# F200s.net
KiCad netlist of a schematic drawn in Altium Designer
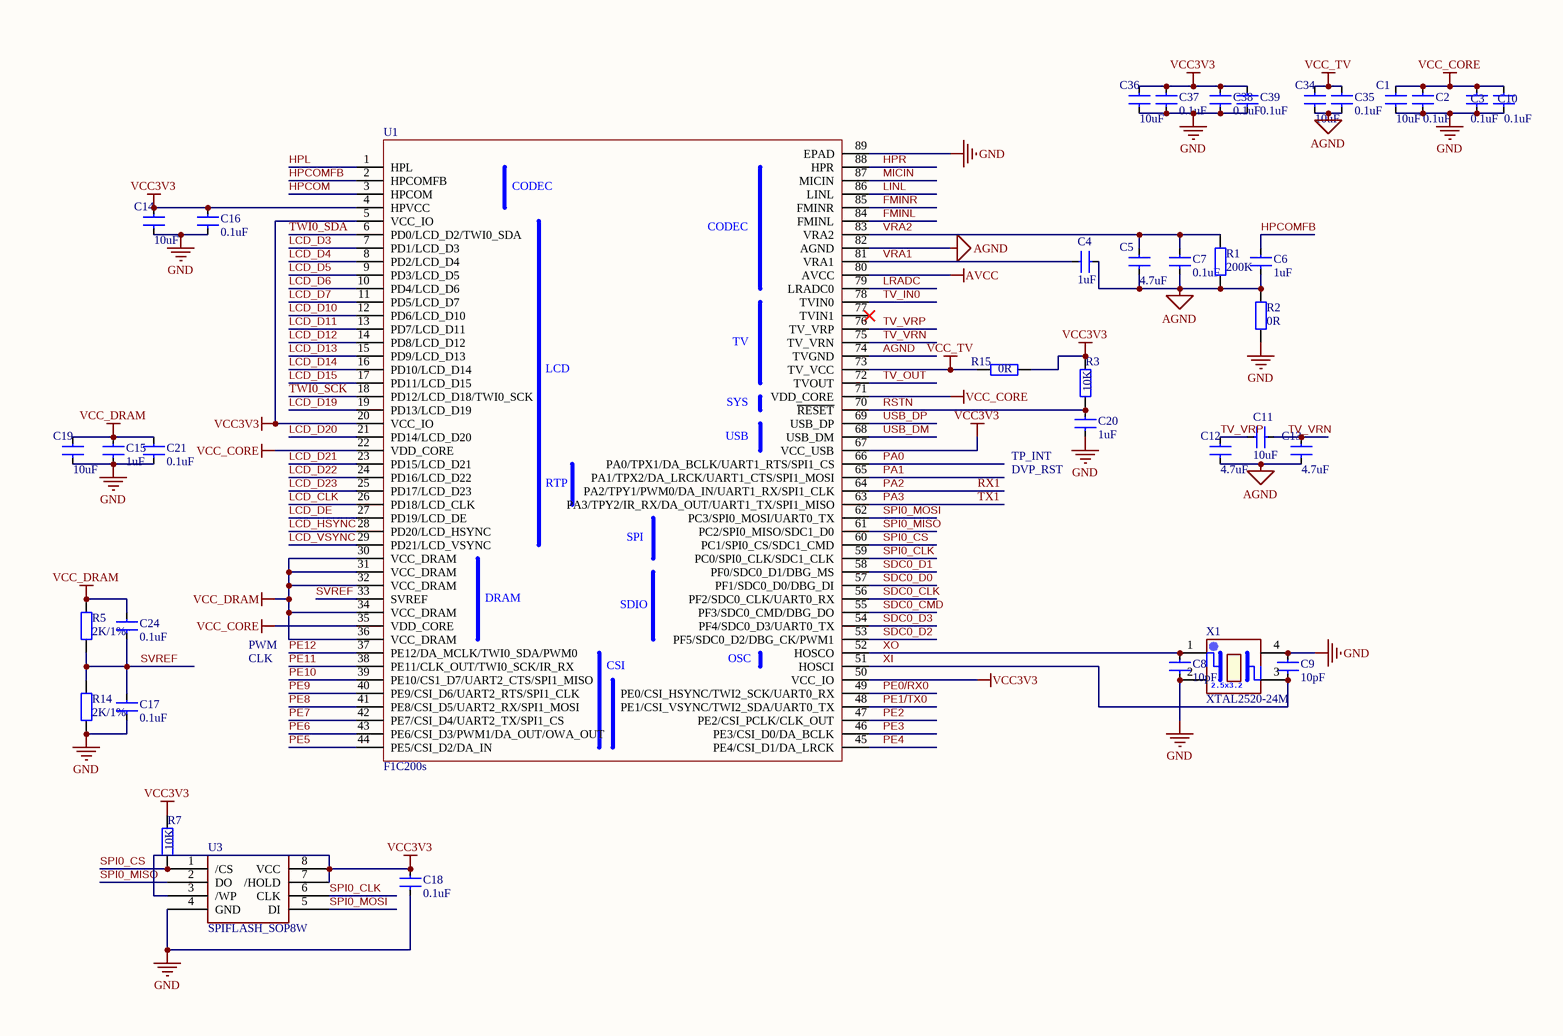
[diagram p0: F200s.SchDoc]

(export (version "E")
  (design (tool "Eeschema 10.0.6"))
  (components
    (comp (ref "C1")
      (value "10uF")
      (footprint "C0402")
      (description "普通小电容")
      (libsource (lib "LIB_MANGO") (part "CAP"))
    )
    (comp (ref "C2")
      (value "0.1uF")
      (footprint "C0402")
      (description "普通小电容")
      (libsource (lib "LIB_MANGO") (part "CAP"))
    )
    (comp (ref "C3")
      (value "0.1uF")
      (footprint "C0402")
      (description "普通小电容")
      (libsource (lib "LIB_MANGO") (part "CAP"))
    )
    (comp (ref "C4")
      (value "1uF")
      (footprint "C0402")
      (description "普通小电容")
      (libsource (lib "LIB_MANGO") (part "CAP"))
    )
    (comp (ref "C5")
      (value "4.7uF")
      (footprint "C0402")
      (description "普通小电容")
      (libsource (lib "LIB_MANGO") (part "CAP"))
    )
    (comp (ref "C6")
      (value "1uF")
      (footprint "C0402")
      (description "普通小电容")
      (libsource (lib "LIB_MANGO") (part "CAP"))
    )
    (comp (ref "C7")
      (value "0.1uF")
      (footprint "C0402")
      (description "普通小电容")
      (libsource (lib "LIB_MANGO") (part "CAP"))
    )
    (comp (ref "C8")
      (value "10pF")
      (footprint "C0402")
      (description "普通小电容")
      (libsource (lib "LIB_MANGO") (part "CAP"))
    )
    (comp (ref "C9")
      (value "10pF")
      (footprint "C0402")
      (description "普通小电容")
      (libsource (lib "LIB_MANGO") (part "CAP"))
    )
    (comp (ref "C10")
      (value "0.1uF")
      (footprint "C0402")
      (description "普通小电容")
      (libsource (lib "LIB_MANGO") (part "CAP"))
    )
    (comp (ref "C11")
      (value "10uF")
      (footprint "C0402")
      (description "普通小电容")
      (libsource (lib "LIB_MANGO") (part "CAP"))
    )
    (comp (ref "C12")
      (value "4.7uF")
      (footprint "C0402")
      (description "普通小电容")
      (libsource (lib "LIB_MANGO") (part "CAP"))
    )
    (comp (ref "C13")
      (value "4.7uF")
      (footprint "C0402")
      (description "普通小电容")
      (libsource (lib "LIB_MANGO") (part "CAP"))
    )
    (comp (ref "C14")
      (value "10uF")
      (footprint "C0402")
      (description "普通小电容")
      (libsource (lib "LIB_MANGO") (part "CAP"))
    )
    (comp (ref "C15")
      (value "1uF")
      (footprint "C0402")
      (description "普通小电容")
      (libsource (lib "LIB_MANGO") (part "CAP"))
    )
    (comp (ref "C16")
      (value "0.1uF")
      (footprint "C0402")
      (description "普通小电容")
      (libsource (lib "LIB_MANGO") (part "CAP"))
    )
    (comp (ref "C17")
      (value "0.1uF")
      (footprint "C0402")
      (description "普通小电容")
      (libsource (lib "LIB_MANGO") (part "CAP"))
    )
    (comp (ref "C18")
      (value "0.1uF")
      (footprint "C0402")
      (description "普通小电容")
      (libsource (lib "LIB_MANGO") (part "CAP"))
    )
    (comp (ref "C19")
      (value "10uF")
      (footprint "C0402")
      (description "普通小电容")
      (libsource (lib "LIB_MANGO") (part "CAP"))
    )
    (comp (ref "C20")
      (value "1uF")
      (footprint "C0402")
      (description "普通小电容")
      (libsource (lib "LIB_MANGO") (part "CAP"))
    )
    (comp (ref "C21")
      (value "0.1uF")
      (footprint "C0402")
      (description "普通小电容")
      (libsource (lib "LIB_MANGO") (part "CAP"))
    )
    (comp (ref "C24")
      (value "0.1uF")
      (footprint "C0402")
      (description "普通小电容")
      (libsource (lib "LIB_MANGO") (part "CAP"))
    )
    (comp (ref "C34")
      (value "10uF")
      (footprint "C0402")
      (description "普通小电容")
      (libsource (lib "LIB_MANGO") (part "CAP"))
    )
    (comp (ref "C35")
      (value "0.1uF")
      (footprint "C0402")
      (description "普通小电容")
      (libsource (lib "LIB_MANGO") (part "CAP"))
    )
    (comp (ref "C36")
      (value "10uF")
      (footprint "C0402")
      (description "普通小电容")
      (libsource (lib "LIB_MANGO") (part "CAP"))
    )
    (comp (ref "C37")
      (value "0.1uF")
      (footprint "C0402")
      (description "普通小电容")
      (libsource (lib "LIB_MANGO") (part "CAP"))
    )
    (comp (ref "C38")
      (value "0.1uF")
      (footprint "C0402")
      (description "普通小电容")
      (libsource (lib "LIB_MANGO") (part "CAP"))
    )
    (comp (ref "C39")
      (value "0.1uF")
      (footprint "C0402")
      (description "普通小电容")
      (libsource (lib "LIB_MANGO") (part "CAP"))
    )
    (comp (ref "R1")
      (value "200K")
      (footprint "R0402")
      (description "普通电阻")
      (libsource (lib "LIB_MANGO") (part "RES"))
    )
    (comp (ref "R2")
      (value "0R")
      (footprint "R0402")
      (description "普通电阻")
      (libsource (lib "LIB_MANGO") (part "RES"))
    )
    (comp (ref "R3")
      (value "10K")
      (footprint "R0402")
      (description "普通电阻")
      (libsource (lib "LIB_MANGO") (part "RES"))
    )
    (comp (ref "R5")
      (value "2K/1%")
      (footprint "R0402")
      (description "普通电阻")
      (libsource (lib "LIB_MANGO") (part "RES"))
    )
    (comp (ref "R7")
      (value "10K")
      (footprint "R0402")
      (description "普通电阻")
      (libsource (lib "LIB_MANGO") (part "RES"))
    )
    (comp (ref "R14")
      (value "2K/1%")
      (footprint "R0402")
      (description "普通电阻")
      (libsource (lib "LIB_MANGO") (part "RES"))
    )
    (comp (ref "R15")
      (value "0R")
      (footprint "R0402")
      (description "普通电阻")
      (libsource (lib "") (part "RES_1"))
    )
    (comp (ref "U1")
      (value "F1C200s")
      (footprint "QFN40P1000X1000X85_HS-89N")
      (libsource (lib "A") (part "F1C200s"))
    )
    (comp (ref "U3")
      (value "SPIFLASH_SOP8W")
      (footprint "WSON-SPIFLASH")
      (libsource (lib "LIB_MANGO") (part "SPIFLASH_SOP8W"))
    )
    (comp (ref "X1")
      (value "XTAL2520-24M")
      (footprint "XTAL2520")
      (libsource (lib "LIB_MANGO") (part "XTAL3225"))
    )
  )
  (nets
    (net (code "1") (name "/FMINL") (class "Default")
      (node (ref "U1") (pin "84") (pinfunction "FMINL_84") (pintype "passive"))
    )
    (net (code "2") (name "/FMINR") (class "Default")
      (node (ref "U1") (pin "85") (pinfunction "FMINR_85") (pintype "passive"))
    )
    (net (code "3") (name "/HPCOM") (class "Default")
      (node (ref "U1") (pin "3") (pinfunction "HPCOM_3") (pintype "passive"))
    )
    (net (code "4") (name "/HPCOMFB") (class "Default")
      (node (ref "C6") (pin "1") (pinfunction "1_1") (pintype "passive"))
      (node (ref "U1") (pin "2") (pinfunction "HPCOMFB_2") (pintype "passive"))
    )
    (net (code "5") (name "/HPL") (class "Default")
      (node (ref "U1") (pin "1") (pinfunction "HPL_1") (pintype "passive"))
    )
    (net (code "6") (name "/HPR") (class "Default")
      (node (ref "U1") (pin "88") (pinfunction "HPR_88") (pintype "passive"))
    )
    (net (code "7") (name "/LCD_CLK") (class "Default")
      (node (ref "U1") (pin "26") (pinfunction "PD18/LCD_CLK_26") (pintype "passive"))
    )
    (net (code "8") (name "/LCD_D3") (class "Default")
      (node (ref "U1") (pin "7") (pinfunction "PD1/LCD_D3_7") (pintype "passive"))
    )
    (net (code "9") (name "/LCD_D4") (class "Default")
      (node (ref "U1") (pin "8") (pinfunction "PD2/LCD_D4_8") (pintype "passive"))
    )
    (net (code "10") (name "/LCD_D5") (class "Default")
      (node (ref "U1") (pin "9") (pinfunction "PD3/LCD_D5_9") (pintype "passive"))
    )
    (net (code "11") (name "/LCD_D6") (class "Default")
      (node (ref "U1") (pin "10") (pinfunction "PD4/LCD_D6_10") (pintype "passive"))
    )
    (net (code "12") (name "/LCD_D7") (class "Default")
      (node (ref "U1") (pin "11") (pinfunction "PD5/LCD_D7_11") (pintype "passive"))
    )
    (net (code "13") (name "/LCD_D10") (class "Default")
      (node (ref "U1") (pin "12") (pinfunction "PD6/LCD_D10_12") (pintype "passive"))
    )
    (net (code "14") (name "/LCD_D11") (class "Default")
      (node (ref "U1") (pin "13") (pinfunction "PD7/LCD_D11_13") (pintype "passive"))
    )
    (net (code "15") (name "/LCD_D12") (class "Default")
      (node (ref "U1") (pin "14") (pinfunction "PD8/LCD_D12_14") (pintype "passive"))
    )
    (net (code "16") (name "/LCD_D13") (class "Default")
      (node (ref "U1") (pin "15") (pinfunction "PD9/LCD_D13_15") (pintype "passive"))
    )
    (net (code "17") (name "/LCD_D14") (class "Default")
      (node (ref "U1") (pin "16") (pinfunction "PD10/LCD_D14_16") (pintype "passive"))
    )
    (net (code "18") (name "/LCD_D15") (class "Default")
      (node (ref "U1") (pin "17") (pinfunction "PD11/LCD_D15_17") (pintype "passive"))
    )
    (net (code "19") (name "/LCD_D19") (class "Default")
      (node (ref "U1") (pin "19") (pinfunction "PD13/LCD_D19_19") (pintype "passive"))
    )
    (net (code "20") (name "/LCD_D20") (class "Default")
      (node (ref "U1") (pin "21") (pinfunction "PD14/LCD_D20_21") (pintype "passive"))
    )
    (net (code "21") (name "/LCD_D21") (class "Default")
      (node (ref "U1") (pin "23") (pinfunction "PD15/LCD_D21_23") (pintype "passive"))
    )
    (net (code "22") (name "/LCD_D22") (class "Default")
      (node (ref "U1") (pin "24") (pinfunction "PD16/LCD_D22_24") (pintype "passive"))
    )
    (net (code "23") (name "/LCD_D23") (class "Default")
      (node (ref "U1") (pin "25") (pinfunction "PD17/LCD_D23_25") (pintype "passive"))
    )
    (net (code "24") (name "/LCD_DE") (class "Default")
      (node (ref "U1") (pin "27") (pinfunction "PD19/LCD_DE_27") (pintype "passive"))
    )
    (net (code "25") (name "/LCD_HSYNC") (class "Default")
      (node (ref "U1") (pin "28") (pinfunction "PD20/LCD_HSYNC_28") (pintype "passive"))
    )
    (net (code "26") (name "/LCD_VSYNC") (class "Default")
      (node (ref "U1") (pin "29") (pinfunction "PD21/LCD_VSYNC_29") (pintype "passive"))
    )
    (net (code "27") (name "/LINL") (class "Default")
      (node (ref "U1") (pin "86") (pinfunction "LINL_86") (pintype "passive"))
    )
    (net (code "28") (name "/LRADC") (class "Default")
      (node (ref "U1") (pin "79") (pinfunction "LRADC0_79") (pintype "passive"))
    )
    (net (code "29") (name "/MICIN") (class "Default")
      (node (ref "U1") (pin "87") (pinfunction "MICIN_87") (pintype "passive"))
    )
    (net (code "30") (name "/PA0") (class "Default")
      (node (ref "U1") (pin "66") (pinfunction "PA0/TPX1/DA_BCLK/UART1_RTS/SPI1_CS_66") (pintype "passive"))
    )
    (net (code "31") (name "/PA1") (class "Default")
      (node (ref "U1") (pin "65") (pinfunction "PA1/TPX2/DA_LRCK/UART1_CTS/SPI1_MOSI_65") (pintype "passive"))
    )
    (net (code "32") (name "/PA2") (class "Default")
      (node (ref "U1") (pin "64") (pinfunction "PA2/TPY1/PWM0/DA_IN/UART1_RX/SPI1_CLK_64") (pintype "passive"))
    )
    (net (code "33") (name "/PA3") (class "Default")
      (node (ref "U1") (pin "63") (pinfunction "PA3/TPY2/IR_RX/DA_OUT/UART1_TX/SPI1_MISO_63") (pintype "passive"))
    )
    (net (code "34") (name "/PE0{slash}RX0") (class "Default")
      (node (ref "U1") (pin "49") (pinfunction "PE0/CSI_HSYNC/TWI2_SCK/UART0_RX_49") (pintype "passive"))
    )
    (net (code "35") (name "/PE1{slash}TX0") (class "Default")
      (node (ref "U1") (pin "48") (pinfunction "PE1/CSI_VSYNC/TWI2_SDA/UART0_TX_48") (pintype "passive"))
    )
    (net (code "36") (name "/PE2") (class "Default")
      (node (ref "U1") (pin "47") (pinfunction "PE2/CSI_PCLK/CLK_OUT_47") (pintype "passive"))
    )
    (net (code "37") (name "/PE3") (class "Default")
      (node (ref "U1") (pin "46") (pinfunction "PE3/CSI_D0/DA_BCLK_46") (pintype "passive"))
    )
    (net (code "38") (name "/PE4") (class "Default")
      (node (ref "U1") (pin "45") (pinfunction "PE4/CSI_D1/DA_LRCK_45") (pintype "passive"))
    )
    (net (code "39") (name "/PE5") (class "Default")
      (node (ref "U1") (pin "44") (pinfunction "PE5/CSI_D2/DA_IN_44") (pintype "passive"))
    )
    (net (code "40") (name "/PE6") (class "Default")
      (node (ref "U1") (pin "43") (pinfunction "PE6/CSI_D3/PWM1/DA_OUT/OWA_OUT_43") (pintype "passive"))
    )
    (net (code "41") (name "/PE7") (class "Default")
      (node (ref "U1") (pin "42") (pinfunction "PE7/CSI_D4/UART2_TX/SPI1_CS_42") (pintype "passive"))
    )
    (net (code "42") (name "/PE8") (class "Default")
      (node (ref "U1") (pin "41") (pinfunction "PE8/CSI_D5/UART2_RX/SPI1_MOSI_41") (pintype "passive"))
    )
    (net (code "43") (name "/PE9") (class "Default")
      (node (ref "U1") (pin "40") (pinfunction "PE9/CSI_D6/UART2_RTS/SPI1_CLK_40") (pintype "passive"))
    )
    (net (code "44") (name "/PE10") (class "Default")
      (node (ref "U1") (pin "39") (pinfunction "PE10/CS1_D7/UART2_CTS/SPI1_MISO_39") (pintype "passive"))
    )
    (net (code "45") (name "/PE11") (class "Default")
      (node (ref "U1") (pin "38") (pinfunction "PE11/CLK_OUT/TWI0_SCK/IR_RX_38") (pintype "passive"))
    )
    (net (code "46") (name "/PE12") (class "Default")
      (node (ref "U1") (pin "37") (pinfunction "PE12/DA_MCLK/TWI0_SDA/PWM0_37") (pintype "passive"))
    )
    (net (code "47") (name "/RSTN") (class "Default")
      (node (ref "C20") (pin "1") (pinfunction "1_1") (pintype "passive"))
      (node (ref "R3") (pin "1") (pinfunction "1_1") (pintype "passive"))
      (node (ref "U1") (pin "70") (pinfunction "~{RESET}_70") (pintype "passive"))
    )
    (net (code "48") (name "/SDC0_CLK") (class "Default")
      (node (ref "U1") (pin "56") (pinfunction "PF2/SDC0_CLK/UART0_RX_56") (pintype "passive"))
    )
    (net (code "49") (name "/SDC0_CMD") (class "Default")
      (node (ref "U1") (pin "55") (pinfunction "PF3/SDC0_CMD/DBG_DO_55") (pintype "passive"))
    )
    (net (code "50") (name "/SDC0_D0") (class "Default")
      (node (ref "U1") (pin "57") (pinfunction "PF1/SDC0_D0/DBG_DI_57") (pintype "passive"))
    )
    (net (code "51") (name "/SDC0_D1") (class "Default")
      (node (ref "U1") (pin "58") (pinfunction "PF0/SDC0_D1/DBG_MS_58") (pintype "passive"))
    )
    (net (code "52") (name "/SDC0_D2") (class "Default")
      (node (ref "U1") (pin "53") (pinfunction "PF5/SDC0_D2/DBG_CK/PWM1_53") (pintype "passive"))
    )
    (net (code "53") (name "/SDC0_D3") (class "Default")
      (node (ref "U1") (pin "54") (pinfunction "PF4/SDC0_D3/UART0_TX_54") (pintype "passive"))
    )
    (net (code "54") (name "/SPI0_CLK") (class "Default")
      (node (ref "U1") (pin "59") (pinfunction "PC0/SPI0_CLK/SDC1_CLK_59") (pintype "passive"))
      (node (ref "U3") (pin "6") (pinfunction "CLK_6") (pintype "passive"))
    )
    (net (code "55") (name "/SPI0_CS") (class "Default")
      (node (ref "R7") (pin "1") (pinfunction "1_1") (pintype "passive"))
      (node (ref "U1") (pin "60") (pinfunction "PC1/SPI0_CS/SDC1_CMD_60") (pintype "passive"))
      (node (ref "U3") (pin "1") (pinfunction "/CS_1") (pintype "passive"))
    )
    (net (code "56") (name "/SPI0_MISO") (class "Default")
      (node (ref "U1") (pin "61") (pinfunction "PC2/SPI0_MISO/SDC1_D0_61") (pintype "passive"))
      (node (ref "U3") (pin "2") (pinfunction "DO_2") (pintype "passive"))
    )
    (net (code "57") (name "/SPI0_MOSI") (class "Default")
      (node (ref "U1") (pin "62") (pinfunction "PC3/SPI0_MOSI/UART0_TX_62") (pintype "passive"))
      (node (ref "U3") (pin "5") (pinfunction "DI_5") (pintype "passive"))
    )
    (net (code "58") (name "/SVREF") (class "Default")
      (node (ref "C17") (pin "2") (pinfunction "2_2") (pintype "passive"))
      (node (ref "C24") (pin "1") (pinfunction "1_1") (pintype "passive"))
      (node (ref "R14") (pin "2") (pinfunction "2_2") (pintype "passive"))
      (node (ref "R5") (pin "1") (pinfunction "1_1") (pintype "passive"))
      (node (ref "U1") (pin "33") (pinfunction "SVREF_33") (pintype "passive"))
    )
    (net (code "59") (name "/TV_IN0") (class "Default")
      (node (ref "U1") (pin "78") (pinfunction "TVIN0_78") (pintype "passive"))
    )
    (net (code "60") (name "/TV_OUT") (class "Default")
      (node (ref "U1") (pin "72") (pinfunction "TVOUT_72") (pintype "passive"))
    )
    (net (code "61") (name "/TV_VRN") (class "Default")
      (node (ref "C11") (pin "1") (pinfunction "1_1") (pintype "passive"))
      (node (ref "C13") (pin "2") (pinfunction "2_2") (pintype "passive"))
      (node (ref "U1") (pin "75") (pinfunction "TV_VRN_75") (pintype "passive"))
    )
    (net (code "62") (name "/TV_VRP") (class "Default")
      (node (ref "C11") (pin "2") (pinfunction "2_2") (pintype "passive"))
      (node (ref "C12") (pin "2") (pinfunction "2_2") (pintype "passive"))
      (node (ref "U1") (pin "76") (pinfunction "TV_VRP_76") (pintype "passive"))
    )
    (net (code "63") (name "/TWI0_SCK") (class "Default")
      (node (ref "U1") (pin "18") (pinfunction "PD12/LCD_D18/TWI0_SCK_18") (pintype "passive"))
    )
    (net (code "64") (name "/TWI0_SDA") (class "Default")
      (node (ref "U1") (pin "6") (pinfunction "PD0/LCD_D2/TWI0_SDA_6") (pintype "passive"))
    )
    (net (code "65") (name "/USB_DM") (class "Default")
      (node (ref "U1") (pin "68") (pinfunction "USB_DM_68") (pintype "passive"))
    )
    (net (code "66") (name "/USB_DP") (class "Default")
      (node (ref "U1") (pin "69") (pinfunction "USB_DP_69") (pintype "passive"))
    )
    (net (code "67") (name "/VRA1") (class "Default")
      (node (ref "C4") (pin "1") (pinfunction "1_1") (pintype "passive"))
      (node (ref "U1") (pin "81") (pinfunction "VRA1_81") (pintype "passive"))
    )
    (net (code "68") (name "/VRA2") (class "Default")
      (node (ref "C5") (pin "2") (pinfunction "2_2") (pintype "passive"))
      (node (ref "C7") (pin "2") (pinfunction "2_2") (pintype "passive"))
      (node (ref "R1") (pin "2") (pinfunction "2_2") (pintype "passive"))
      (node (ref "U1") (pin "83") (pinfunction "VRA2_83") (pintype "passive"))
    )
    (net (code "69") (name "/XI") (class "Default")
      (node (ref "C9") (pin "1") (pinfunction "1_1") (pintype "passive"))
      (node (ref "U1") (pin "51") (pinfunction "HOSCI_51") (pintype "passive"))
      (node (ref "X1") (pin "3") (pinfunction "X2_3") (pintype "passive"))
    )
    (net (code "70") (name "/XO") (class "Default")
      (node (ref "C8") (pin "2") (pinfunction "2_2") (pintype "passive"))
      (node (ref "U1") (pin "52") (pinfunction "HOSCO_52") (pintype "passive"))
      (node (ref "X1") (pin "1") (pinfunction "X1_1") (pintype "passive"))
    )
    (net (code "71") (name "AGND") (class "Default")
      (node (ref "C12") (pin "1") (pinfunction "1_1") (pintype "passive"))
      (node (ref "C13") (pin "1") (pinfunction "1_1") (pintype "passive"))
      (node (ref "C34") (pin "1") (pinfunction "1_1") (pintype "passive"))
      (node (ref "C35") (pin "1") (pinfunction "1_1") (pintype "passive"))
      (node (ref "C4") (pin "2") (pinfunction "2_2") (pintype "passive"))
      (node (ref "C5") (pin "1") (pinfunction "1_1") (pintype "passive"))
      (node (ref "C6") (pin "2") (pinfunction "2_2") (pintype "passive"))
      (node (ref "C7") (pin "1") (pinfunction "1_1") (pintype "passive"))
      (node (ref "R1") (pin "1") (pinfunction "1_1") (pintype "passive"))
      (node (ref "R2") (pin "2") (pinfunction "2_2") (pintype "passive"))
      (node (ref "U1") (pin "74") (pinfunction "TVGND_74") (pintype "passive"))
      (node (ref "U1") (pin "82") (pinfunction "AGND_82") (pintype "passive"))
    )
    (net (code "72") (name "AVCC") (class "Default")
      (node (ref "U1") (pin "80") (pinfunction "AVCC_80") (pintype "passive"))
    )
    (net (code "73") (name "GND") (class "Default")
      (node (ref "C1") (pin "1") (pinfunction "1_1") (pintype "passive"))
      (node (ref "C10") (pin "1") (pinfunction "1_1") (pintype "passive"))
      (node (ref "C14") (pin "1") (pinfunction "1_1") (pintype "passive"))
      (node (ref "C15") (pin "1") (pinfunction "1_1") (pintype "passive"))
      (node (ref "C16") (pin "1") (pinfunction "1_1") (pintype "passive"))
      (node (ref "C17") (pin "1") (pinfunction "1_1") (pintype "passive"))
      (node (ref "C18") (pin "1") (pinfunction "1_1") (pintype "passive"))
      (node (ref "C19") (pin "1") (pinfunction "1_1") (pintype "passive"))
      (node (ref "C2") (pin "1") (pinfunction "1_1") (pintype "passive"))
      (node (ref "C20") (pin "2") (pinfunction "2_2") (pintype "passive"))
      (node (ref "C21") (pin "1") (pinfunction "1_1") (pintype "passive"))
      (node (ref "C3") (pin "1") (pinfunction "1_1") (pintype "passive"))
      (node (ref "C36") (pin "1") (pinfunction "1_1") (pintype "passive"))
      (node (ref "C37") (pin "1") (pinfunction "1_1") (pintype "passive"))
      (node (ref "C38") (pin "1") (pinfunction "1_1") (pintype "passive"))
      (node (ref "C39") (pin "1") (pinfunction "1_1") (pintype "passive"))
      (node (ref "C8") (pin "1") (pinfunction "1_1") (pintype "passive"))
      (node (ref "C9") (pin "2") (pinfunction "2_2") (pintype "passive"))
      (node (ref "R14") (pin "1") (pinfunction "1_1") (pintype "passive"))
      (node (ref "R2") (pin "1") (pinfunction "1_1") (pintype "passive"))
      (node (ref "U1") (pin "89") (pinfunction "EPAD_89") (pintype "passive"))
      (node (ref "U3") (pin "4") (pinfunction "GND_4") (pintype "passive"))
      (node (ref "X1") (pin "2") (pinfunction "NC1_2") (pintype "passive"))
      (node (ref "X1") (pin "4") (pinfunction "NC2_4") (pintype "passive"))
    )
    (net (code "74") (name "VCC3V3") (class "Default")
      (node (ref "C14") (pin "2") (pinfunction "2_2") (pintype "passive"))
      (node (ref "C16") (pin "2") (pinfunction "2_2") (pintype "passive"))
      (node (ref "C18") (pin "2") (pinfunction "2_2") (pintype "passive"))
      (node (ref "C36") (pin "2") (pinfunction "2_2") (pintype "passive"))
      (node (ref "C37") (pin "2") (pinfunction "2_2") (pintype "passive"))
      (node (ref "C38") (pin "2") (pinfunction "2_2") (pintype "passive"))
      (node (ref "C39") (pin "2") (pinfunction "2_2") (pintype "passive"))
      (node (ref "R15") (pin "1") (pinfunction "1_1") (pintype "passive"))
      (node (ref "R3") (pin "2") (pinfunction "2_2") (pintype "passive"))
      (node (ref "R7") (pin "2") (pinfunction "2_2") (pintype "passive"))
      (node (ref "U1") (pin "20") (pinfunction "VCC_IO_20") (pintype "passive"))
      (node (ref "U1") (pin "4") (pinfunction "HPVCC_4") (pintype "passive"))
      (node (ref "U1") (pin "5") (pinfunction "VCC_IO_5") (pintype "passive"))
      (node (ref "U1") (pin "50") (pinfunction "VCC_IO_50") (pintype "passive"))
      (node (ref "U1") (pin "67") (pinfunction "VCC_USB_67") (pintype "passive"))
      (node (ref "U3") (pin "3") (pinfunction "/WP_3") (pintype "passive"))
      (node (ref "U3") (pin "7") (pinfunction "/HOLD_7") (pintype "passive"))
      (node (ref "U3") (pin "8") (pinfunction "VCC_8") (pintype "passive"))
    )
    (net (code "75") (name "VCC_CORE") (class "Default")
      (node (ref "C1") (pin "2") (pinfunction "2_2") (pintype "passive"))
      (node (ref "C10") (pin "2") (pinfunction "2_2") (pintype "passive"))
      (node (ref "C2") (pin "2") (pinfunction "2_2") (pintype "passive"))
      (node (ref "C3") (pin "2") (pinfunction "2_2") (pintype "passive"))
      (node (ref "U1") (pin "22") (pinfunction "VDD_CORE_22") (pintype "passive"))
      (node (ref "U1") (pin "35") (pinfunction "VDD_CORE_35") (pintype "passive"))
      (node (ref "U1") (pin "71") (pinfunction "VDD_CORE_71") (pintype "passive"))
    )
    (net (code "76") (name "VCC_DRAM") (class "Default")
      (node (ref "C15") (pin "2") (pinfunction "2_2") (pintype "passive"))
      (node (ref "C19") (pin "2") (pinfunction "2_2") (pintype "passive"))
      (node (ref "C21") (pin "2") (pinfunction "2_2") (pintype "passive"))
      (node (ref "C24") (pin "2") (pinfunction "2_2") (pintype "passive"))
      (node (ref "R5") (pin "2") (pinfunction "2_2") (pintype "passive"))
      (node (ref "U1") (pin "30") (pinfunction "VCC_DRAM_30") (pintype "passive"))
      (node (ref "U1") (pin "31") (pinfunction "VCC_DRAM_31") (pintype "passive"))
      (node (ref "U1") (pin "32") (pinfunction "VCC_DRAM_32") (pintype "passive"))
      (node (ref "U1") (pin "34") (pinfunction "VCC_DRAM_34") (pintype "passive"))
      (node (ref "U1") (pin "36") (pinfunction "VCC_DRAM_36") (pintype "passive"))
    )
    (net (code "77") (name "VCC_TV") (class "Default")
      (node (ref "C34") (pin "2") (pinfunction "2_2") (pintype "passive"))
      (node (ref "C35") (pin "2") (pinfunction "2_2") (pintype "passive"))
      (node (ref "R15") (pin "2") (pinfunction "2_2") (pintype "passive"))
      (node (ref "U1") (pin "73") (pinfunction "TV_VCC_73") (pintype "passive"))
    )
    (net (code "78") (name "unconnected-(U1-TVIN1-Pad77)") (class "Default")
      (node (ref "U1") (pin "77") (pinfunction "TVIN1_77") (pintype "passive+no_connect"))
    )
  )
)
